# Cable-Test-RJ45-RJ12.net
KiCad netlist of a schematic drawn in EAGLE
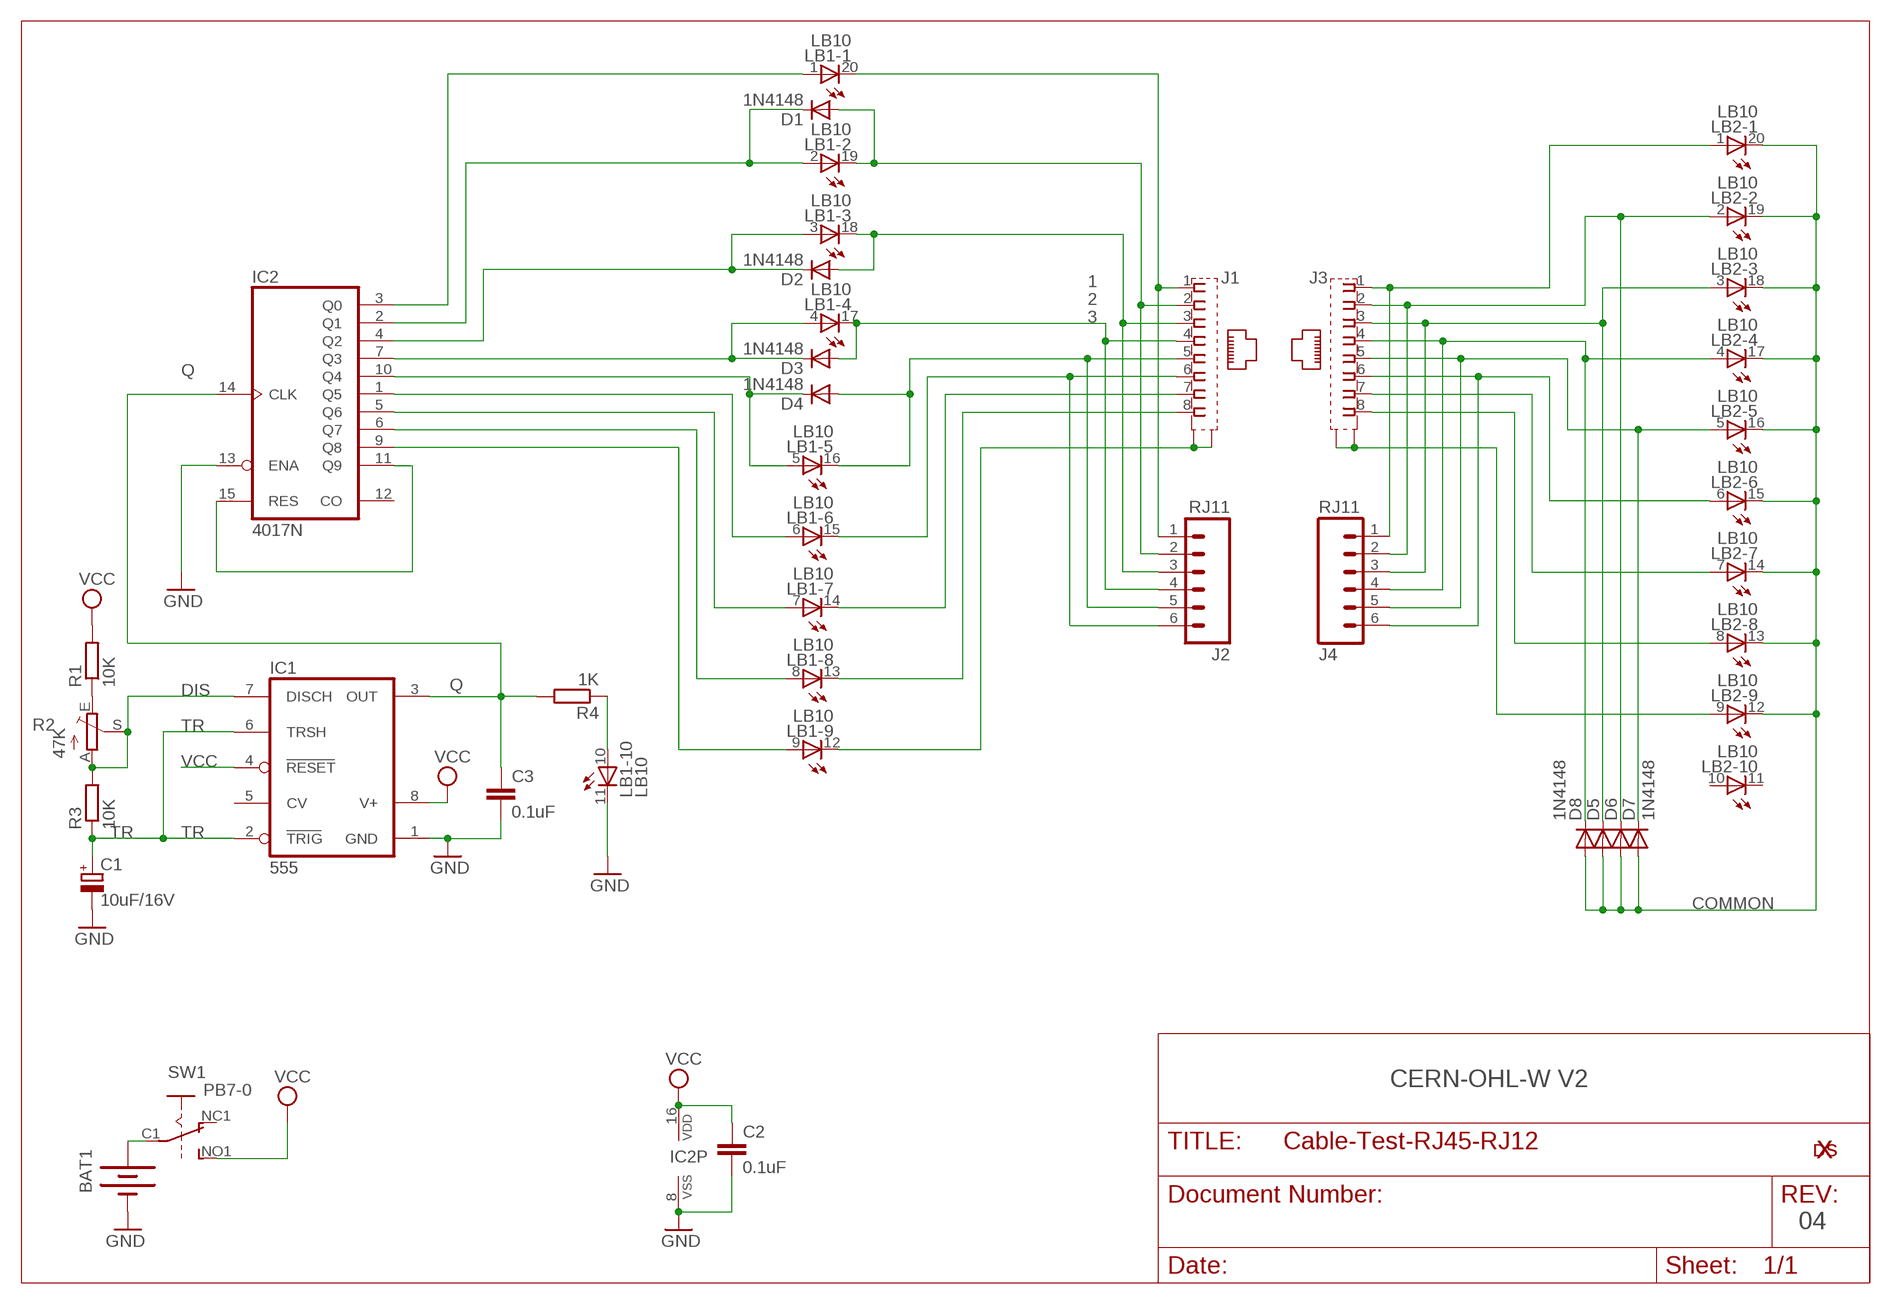
[diagram p0: schematic, sheet 1]

(export (version "E")
  (design (tool "Eeschema 10.0.6"))
  (components
    (comp (ref "$1_23_$")
      (value "XDESIG21")
      (footprint "eagle-import:XDESIG")
      (libsource (lib "eagle-import") (part "XDESIG21"))
    )
    (comp (ref "BAT1")
      (value "BATTERY9V")
      (footprint "eagle-import:BATTCON_9V")
      (libsource (lib "eagle-import") (part "BATTERY9V"))
    )
    (comp (ref "C1")
      (value "10uF/16V")
      (footprint "eagle-import:E2,5-6")
      (libsource (lib "eagle-import") (part "CPOL-EUE2.5-6"))
    )
    (comp (ref "C2")
      (value "0.1uF")
      (footprint "eagle-import:C2.5-2")
      (libsource (lib "eagle-import") (part "C2.5/2"))
    )
    (comp (ref "C3")
      (value "0.1uF")
      (footprint "eagle-import:C2.5-2")
      (libsource (lib "eagle-import") (part "C2.5/2"))
    )
    (comp (ref "D1")
      (value "1N4148")
      (footprint "eagle-import:D-2.5")
      (libsource (lib "eagle-import") (part "DIODE-D-2.5"))
    )
    (comp (ref "D2")
      (value "1N4148")
      (footprint "eagle-import:D-2.5")
      (libsource (lib "eagle-import") (part "DIODE-D-2.5"))
    )
    (comp (ref "D3")
      (value "1N4148")
      (footprint "eagle-import:D-2.5")
      (libsource (lib "eagle-import") (part "DIODE-D-2.5"))
    )
    (comp (ref "D4")
      (value "1N4148")
      (footprint "eagle-import:D-2.5")
      (libsource (lib "eagle-import") (part "DIODE-D-2.5"))
    )
    (comp (ref "D5")
      (value "DIODE-D-2.5")
      (footprint "eagle-import:D-2.5")
      (libsource (lib "eagle-import") (part "DIODE-D-2.5"))
    )
    (comp (ref "D6")
      (value "1N4148")
      (footprint "eagle-import:D-2.5")
      (libsource (lib "eagle-import") (part "DIODE-D-2.5"))
    )
    (comp (ref "D7")
      (value "1N4148")
      (footprint "eagle-import:D-2.5")
      (libsource (lib "eagle-import") (part "DIODE-D-2.5"))
    )
    (comp (ref "D8")
      (value "DIODE-D-2.5")
      (footprint "eagle-import:D-2.5")
      (libsource (lib "eagle-import") (part "DIODE-D-2.5"))
    )
    (comp (ref "IC1")
      (value "555")
      (footprint "eagle-import:DIL08")
      (fields (field (name "MF") "MAXIM") (field (name "MPN") "ICM7555IPA+"))
      (libsource (lib "eagle-import") (part "ICM7555"))
    )
    (comp (ref "IC2")
      (value "4017N")
      (footprint "eagle-import:DIL16")
      (libsource (lib "eagle-import") (part "4017N"))
    )
    (comp (ref "J1")
      (value "555153-1")
      (footprint "eagle-import:555153-1")
      (libsource (lib "eagle-import") (part "555153-1"))
    )
    (comp (ref "J2")
      (value "RJ11")
      (footprint "eagle-import:RJ11-6")
      (libsource (lib "eagle-import") (part "RJ11-6PTH"))
    )
    (comp (ref "J3")
      (value "555153-1")
      (footprint "eagle-import:555153-1")
      (libsource (lib "eagle-import") (part "555153-1"))
    )
    (comp (ref "J4")
      (value "RJ11")
      (footprint "eagle-import:RJ11-6")
      (libsource (lib "eagle-import") (part "RJ11-6PTH"))
    )
    (comp (ref "LB1")
      (value "LB10")
      (footprint "eagle-import:LB10")
      (libsource (lib "eagle-import") (part "LB10"))
    )
    (comp (ref "LB2")
      (value "LB10")
      (footprint "eagle-import:LB10")
      (libsource (lib "eagle-import") (part "LB10"))
    )
    (comp (ref "R1")
      (value "10K")
      (footprint "eagle-import:0204_7")
      (libsource (lib "eagle-import") (part "R-EU_0204/7"))
    )
    (comp (ref "R2")
      (value "47K")
      (footprint "eagle-import:CA6V")
      (libsource (lib "eagle-import") (part "TRIM_EU-CA6V"))
    )
    (comp (ref "R3")
      (value "10K")
      (footprint "eagle-import:0204_7")
      (libsource (lib "eagle-import") (part "R-EU_0204/7"))
    )
    (comp (ref "R4")
      (value "1K")
      (footprint "eagle-import:0204_7")
      (libsource (lib "eagle-import") (part "R-EU_0204/7"))
    )
    (comp (ref "SW1")
      (value "PB7-0")
      (footprint "eagle-import:PB07_0")
      (libsource (lib "eagle-import") (part "PB7-0"))
    )
    (comp (ref "U$6")
      (value "XDESIG5MM")
      (footprint "eagle-import:XDESIG_CU")
      (libsource (lib "eagle-import") (part "XDESIG5MM"))
    )
  )
  (nets
    (net (code "1") (name "/1") (class "Default")
      (node (ref "J1") (pin "1") (pinfunction "1_1") (pintype "passive"))
      (node (ref "J2") (pin "1") (pinfunction "1_1") (pintype "passive"))
      (node (ref "LB1") (pin "20") (pinfunction "C_20") (pintype "passive"))
    )
    (net (code "2") (name "/2") (class "Default")
      (node (ref "D1") (pin "A") (pinfunction "A_A") (pintype "passive"))
      (node (ref "J1") (pin "2") (pinfunction "2_2") (pintype "passive"))
      (node (ref "J2") (pin "2") (pinfunction "2_2") (pintype "passive"))
      (node (ref "LB1") (pin "19") (pinfunction "C_19") (pintype "passive"))
    )
    (net (code "3") (name "/3") (class "Default")
      (node (ref "D2") (pin "A") (pinfunction "A_A") (pintype "passive"))
      (node (ref "J1") (pin "3") (pinfunction "3_3") (pintype "passive"))
      (node (ref "J2") (pin "3") (pinfunction "3_3") (pintype "passive"))
      (node (ref "LB1") (pin "18") (pinfunction "C_18") (pintype "passive"))
    )
    (net (code "4") (name "/COMMON") (class "Default")
      (node (ref "D5") (pin "A") (pinfunction "A_A") (pintype "passive"))
      (node (ref "D6") (pin "A") (pinfunction "A_A") (pintype "passive"))
      (node (ref "D7") (pin "A") (pinfunction "A_A") (pintype "passive"))
      (node (ref "D8") (pin "A") (pinfunction "A_A") (pintype "passive"))
      (node (ref "LB2") (pin "12") (pinfunction "C_12") (pintype "passive"))
      (node (ref "LB2") (pin "13") (pinfunction "C_13") (pintype "passive"))
      (node (ref "LB2") (pin "14") (pinfunction "C_14") (pintype "passive"))
      (node (ref "LB2") (pin "15") (pinfunction "C_15") (pintype "passive"))
      (node (ref "LB2") (pin "16") (pinfunction "C_16") (pintype "passive"))
      (node (ref "LB2") (pin "17") (pinfunction "C_17") (pintype "passive"))
      (node (ref "LB2") (pin "18") (pinfunction "C_18") (pintype "passive"))
      (node (ref "LB2") (pin "19") (pinfunction "C_19") (pintype "passive"))
      (node (ref "LB2") (pin "20") (pinfunction "C_20") (pintype "passive"))
    )
    (net (code "5") (name "/DIS") (class "Default")
      (node (ref "IC1") (pin "7") (pinfunction "DISCH_7") (pintype "input"))
      (node (ref "R2") (pin "A") (pinfunction "A_A") (pintype "passive"))
      (node (ref "R2") (pin "S") (pinfunction "S_S") (pintype "passive"))
      (node (ref "R3") (pin "2") (pinfunction "2_2") (pintype "passive"))
    )
    (net (code "6") (name "/Q") (class "Default")
      (node (ref "C3") (pin "1") (pinfunction "1_1") (pintype "passive"))
      (node (ref "IC1") (pin "3") (pinfunction "OUT_3") (pintype "output"))
      (node (ref "IC2") (pin "14") (pinfunction "CLK_14") (pintype "input"))
      (node (ref "R4") (pin "2") (pinfunction "2_2") (pintype "passive"))
    )
    (net (code "7") (name "/TR") (class "Default")
      (node (ref "C1") (pin "+") (pinfunction "+_+") (pintype "passive"))
      (node (ref "IC1") (pin "2") (pinfunction "TRIG_2") (pintype "bidirectional"))
      (node (ref "IC1") (pin "6") (pinfunction "TRSH_6") (pintype "input"))
      (node (ref "R3") (pin "1") (pinfunction "1_1") (pintype "passive"))
    )
    (net (code "8") (name "GND") (class "Default")
      (node (ref "BAT1") (pin "-") (pinfunction "-_-") (pintype "power_in"))
      (node (ref "C1") (pin "-") (pinfunction "-_-") (pintype "passive"))
      (node (ref "C2") (pin "2") (pinfunction "2_2") (pintype "passive"))
      (node (ref "C3") (pin "2") (pinfunction "2_2") (pintype "passive"))
      (node (ref "IC1") (pin "1") (pinfunction "GND_1") (pintype "power_in"))
      (node (ref "IC2") (pin "13") (pinfunction "ENA_13") (pintype "input"))
      (node (ref "IC2") (pin "8") (pinfunction "VSS_8") (pintype "power_in"))
      (node (ref "LB1") (pin "11") (pinfunction "C_11") (pintype "passive"))
    )
    (net (code "9") (name "Net-(IC2A-Q0)") (class "Default")
      (node (ref "IC2") (pin "3") (pinfunction "Q0_3") (pintype "output"))
      (node (ref "LB1") (pin "1") (pinfunction "A_1") (pintype "passive"))
    )
    (net (code "10") (name "Net-(IC2A-Q1)") (class "Default")
      (node (ref "D1") (pin "C") (pinfunction "C_C") (pintype "passive"))
      (node (ref "IC2") (pin "2") (pinfunction "Q1_2") (pintype "output"))
      (node (ref "LB1") (pin "2") (pinfunction "A_2") (pintype "passive"))
    )
    (net (code "11") (name "Net-(IC2A-Q2)") (class "Default")
      (node (ref "D2") (pin "C") (pinfunction "C_C") (pintype "passive"))
      (node (ref "IC2") (pin "4") (pinfunction "Q2_4") (pintype "output"))
      (node (ref "LB1") (pin "3") (pinfunction "A_3") (pintype "passive"))
    )
    (net (code "12") (name "Net-(IC2A-Q3)") (class "Default")
      (node (ref "D3") (pin "C") (pinfunction "C_C") (pintype "passive"))
      (node (ref "IC2") (pin "7") (pinfunction "Q3_7") (pintype "output"))
      (node (ref "LB1") (pin "4") (pinfunction "A_4") (pintype "passive"))
    )
    (net (code "13") (name "Net-(IC2A-Q4)") (class "Default")
      (node (ref "D4") (pin "C") (pinfunction "C_C") (pintype "passive"))
      (node (ref "IC2") (pin "10") (pinfunction "Q4_10") (pintype "output"))
      (node (ref "LB1") (pin "5") (pinfunction "A_5") (pintype "passive"))
    )
    (net (code "14") (name "Net-(IC2A-Q5)") (class "Default")
      (node (ref "IC2") (pin "1") (pinfunction "Q5_1") (pintype "output"))
      (node (ref "LB1") (pin "6") (pinfunction "A_6") (pintype "passive"))
    )
    (net (code "15") (name "Net-(IC2A-Q6)") (class "Default")
      (node (ref "IC2") (pin "5") (pinfunction "Q6_5") (pintype "output"))
      (node (ref "LB1") (pin "7") (pinfunction "A_7") (pintype "passive"))
    )
    (net (code "16") (name "Net-(IC2A-Q7)") (class "Default")
      (node (ref "IC2") (pin "6") (pinfunction "Q7_6") (pintype "output"))
      (node (ref "LB1") (pin "8") (pinfunction "A_8") (pintype "passive"))
    )
    (net (code "17") (name "Net-(IC2A-Q8)") (class "Default")
      (node (ref "IC2") (pin "9") (pinfunction "Q8_9") (pintype "output"))
      (node (ref "LB1") (pin "9") (pinfunction "A_9") (pintype "passive"))
    )
    (net (code "18") (name "Net-(IC2A-Q9)") (class "Default")
      (node (ref "IC2") (pin "11") (pinfunction "Q9_11") (pintype "output"))
      (node (ref "IC2") (pin "15") (pinfunction "RES_15") (pintype "input"))
    )
    (net (code "19") (name "Net-(J1-S1)") (class "Default")
      (node (ref "J1") (pin "G1") (pinfunction "S1_G1") (pintype "passive"))
      (node (ref "J1") (pin "G2") (pinfunction "S2_G2") (pintype "passive"))
      (node (ref "LB1") (pin "12") (pinfunction "C_12") (pintype "passive"))
    )
    (net (code "20") (name "Net-(J3-S1)") (class "Default")
      (node (ref "J3") (pin "G1") (pinfunction "S1_G1") (pintype "passive"))
      (node (ref "J3") (pin "G2") (pinfunction "S2_G2") (pintype "passive"))
      (node (ref "LB2") (pin "9") (pinfunction "A_9") (pintype "passive"))
    )
    (net (code "21") (name "Net-(LB1B-A)") (class "Default")
      (node (ref "LB1") (pin "10") (pinfunction "A_10") (pintype "passive"))
      (node (ref "R4") (pin "1") (pinfunction "1_1") (pintype "passive"))
    )
    (net (code "22") (name "Net-(LB1E-C)") (class "Default")
      (node (ref "D3") (pin "A") (pinfunction "A_A") (pintype "passive"))
      (node (ref "J1") (pin "4") (pinfunction "4_4") (pintype "passive"))
      (node (ref "J2") (pin "4") (pinfunction "4_4") (pintype "passive"))
      (node (ref "LB1") (pin "17") (pinfunction "C_17") (pintype "passive"))
    )
    (net (code "23") (name "Net-(LB1F-C)") (class "Default")
      (node (ref "D4") (pin "A") (pinfunction "A_A") (pintype "passive"))
      (node (ref "J1") (pin "5") (pinfunction "5_5") (pintype "passive"))
      (node (ref "J2") (pin "5") (pinfunction "5_5") (pintype "passive"))
      (node (ref "LB1") (pin "16") (pinfunction "C_16") (pintype "passive"))
    )
    (net (code "24") (name "Net-(LB1G-C)") (class "Default")
      (node (ref "J1") (pin "6") (pinfunction "6_6") (pintype "passive"))
      (node (ref "J2") (pin "6") (pinfunction "6_6") (pintype "passive"))
      (node (ref "LB1") (pin "15") (pinfunction "C_15") (pintype "passive"))
    )
    (net (code "25") (name "Net-(LB1H-C)") (class "Default")
      (node (ref "J1") (pin "7") (pinfunction "7_7") (pintype "passive"))
      (node (ref "LB1") (pin "14") (pinfunction "C_14") (pintype "passive"))
    )
    (net (code "26") (name "Net-(LB1I-C)") (class "Default")
      (node (ref "J1") (pin "8") (pinfunction "8_8") (pintype "passive"))
      (node (ref "LB1") (pin "13") (pinfunction "C_13") (pintype "passive"))
    )
    (net (code "27") (name "Net-(LB2A-A)") (class "Default")
      (node (ref "J3") (pin "1") (pinfunction "1_1") (pintype "passive"))
      (node (ref "J4") (pin "1") (pinfunction "1_1") (pintype "passive"))
      (node (ref "LB2") (pin "1") (pinfunction "A_1") (pintype "passive"))
    )
    (net (code "28") (name "Net-(LB2C-A)") (class "Default")
      (node (ref "D6") (pin "C") (pinfunction "C_C") (pintype "passive"))
      (node (ref "J3") (pin "2") (pinfunction "2_2") (pintype "passive"))
      (node (ref "J4") (pin "2") (pinfunction "2_2") (pintype "passive"))
      (node (ref "LB2") (pin "2") (pinfunction "A_2") (pintype "passive"))
    )
    (net (code "29") (name "Net-(LB2D-A)") (class "Default")
      (node (ref "D5") (pin "C") (pinfunction "C_C") (pintype "passive"))
      (node (ref "J3") (pin "3") (pinfunction "3_3") (pintype "passive"))
      (node (ref "J4") (pin "3") (pinfunction "3_3") (pintype "passive"))
      (node (ref "LB2") (pin "3") (pinfunction "A_3") (pintype "passive"))
    )
    (net (code "30") (name "Net-(LB2E-A)") (class "Default")
      (node (ref "D8") (pin "C") (pinfunction "C_C") (pintype "passive"))
      (node (ref "J3") (pin "4") (pinfunction "4_4") (pintype "passive"))
      (node (ref "J4") (pin "4") (pinfunction "4_4") (pintype "passive"))
      (node (ref "LB2") (pin "4") (pinfunction "A_4") (pintype "passive"))
    )
    (net (code "31") (name "Net-(LB2F-A)") (class "Default")
      (node (ref "D7") (pin "C") (pinfunction "C_C") (pintype "passive"))
      (node (ref "J3") (pin "5") (pinfunction "5_5") (pintype "passive"))
      (node (ref "J4") (pin "5") (pinfunction "5_5") (pintype "passive"))
      (node (ref "LB2") (pin "5") (pinfunction "A_5") (pintype "passive"))
    )
    (net (code "32") (name "Net-(LB2G-A)") (class "Default")
      (node (ref "J3") (pin "6") (pinfunction "6_6") (pintype "passive"))
      (node (ref "J4") (pin "6") (pinfunction "6_6") (pintype "passive"))
      (node (ref "LB2") (pin "6") (pinfunction "A_6") (pintype "passive"))
    )
    (net (code "33") (name "Net-(LB2H-A)") (class "Default")
      (node (ref "J3") (pin "7") (pinfunction "7_7") (pintype "passive"))
      (node (ref "LB2") (pin "7") (pinfunction "A_7") (pintype "passive"))
    )
    (net (code "34") (name "Net-(LB2I-A)") (class "Default")
      (node (ref "J3") (pin "8") (pinfunction "8_8") (pintype "passive"))
      (node (ref "LB2") (pin "8") (pinfunction "A_8") (pintype "passive"))
    )
    (net (code "35") (name "Net-(R1-Pad1)") (class "Default")
      (node (ref "R1") (pin "1") (pinfunction "1_1") (pintype "passive"))
      (node (ref "R2") (pin "E") (pinfunction "E_E") (pintype "passive"))
    )
    (net (code "36") (name "Net-(SW1A-P)") (class "Default")
      (node (ref "BAT1") (pin "+") (pinfunction "+_+") (pintype "power_in"))
      (node (ref "SW1") (pin "C1") (pinfunction "P_C1") (pintype "passive"))
    )
    (net (code "37") (name "VCC") (class "Default")
      (node (ref "C2") (pin "1") (pinfunction "1_1") (pintype "passive"))
      (node (ref "IC1") (pin "4") (pinfunction "RESET_4") (pintype "input"))
      (node (ref "IC1") (pin "8") (pinfunction "V+_8") (pintype "power_in"))
      (node (ref "IC2") (pin "16") (pinfunction "VDD_16") (pintype "power_in"))
      (node (ref "R1") (pin "2") (pinfunction "2_2") (pintype "passive"))
      (node (ref "SW1") (pin "NO1") (pinfunction "S_NO1") (pintype "passive"))
    )
    (net (code "38") (name "unconnected-(IC1-CV-Pad5)") (class "Default")
      (node (ref "IC1") (pin "5") (pinfunction "CV_5") (pintype "passive"))
    )
    (net (code "39") (name "unconnected-(IC2A-CO-Pad12)") (class "Default")
      (node (ref "IC2") (pin "12") (pinfunction "CO_12") (pintype "output"))
    )
    (net (code "40") (name "unconnected-(LB2B-A-Pad10)") (class "Default")
      (node (ref "LB2") (pin "10") (pinfunction "A_10") (pintype "passive"))
    )
    (net (code "41") (name "unconnected-(LB2B-C-Pad11)") (class "Default")
      (node (ref "LB2") (pin "11") (pinfunction "C_11") (pintype "passive"))
    )
    (net (code "42") (name "unconnected-(SW1A-O-PadNC1)") (class "Default")
      (node (ref "SW1") (pin "NC1") (pinfunction "O_NC1") (pintype "passive"))
    )
  )
)
